# Sheet2.net
KiCad netlist of a schematic drawn in Altium Designer
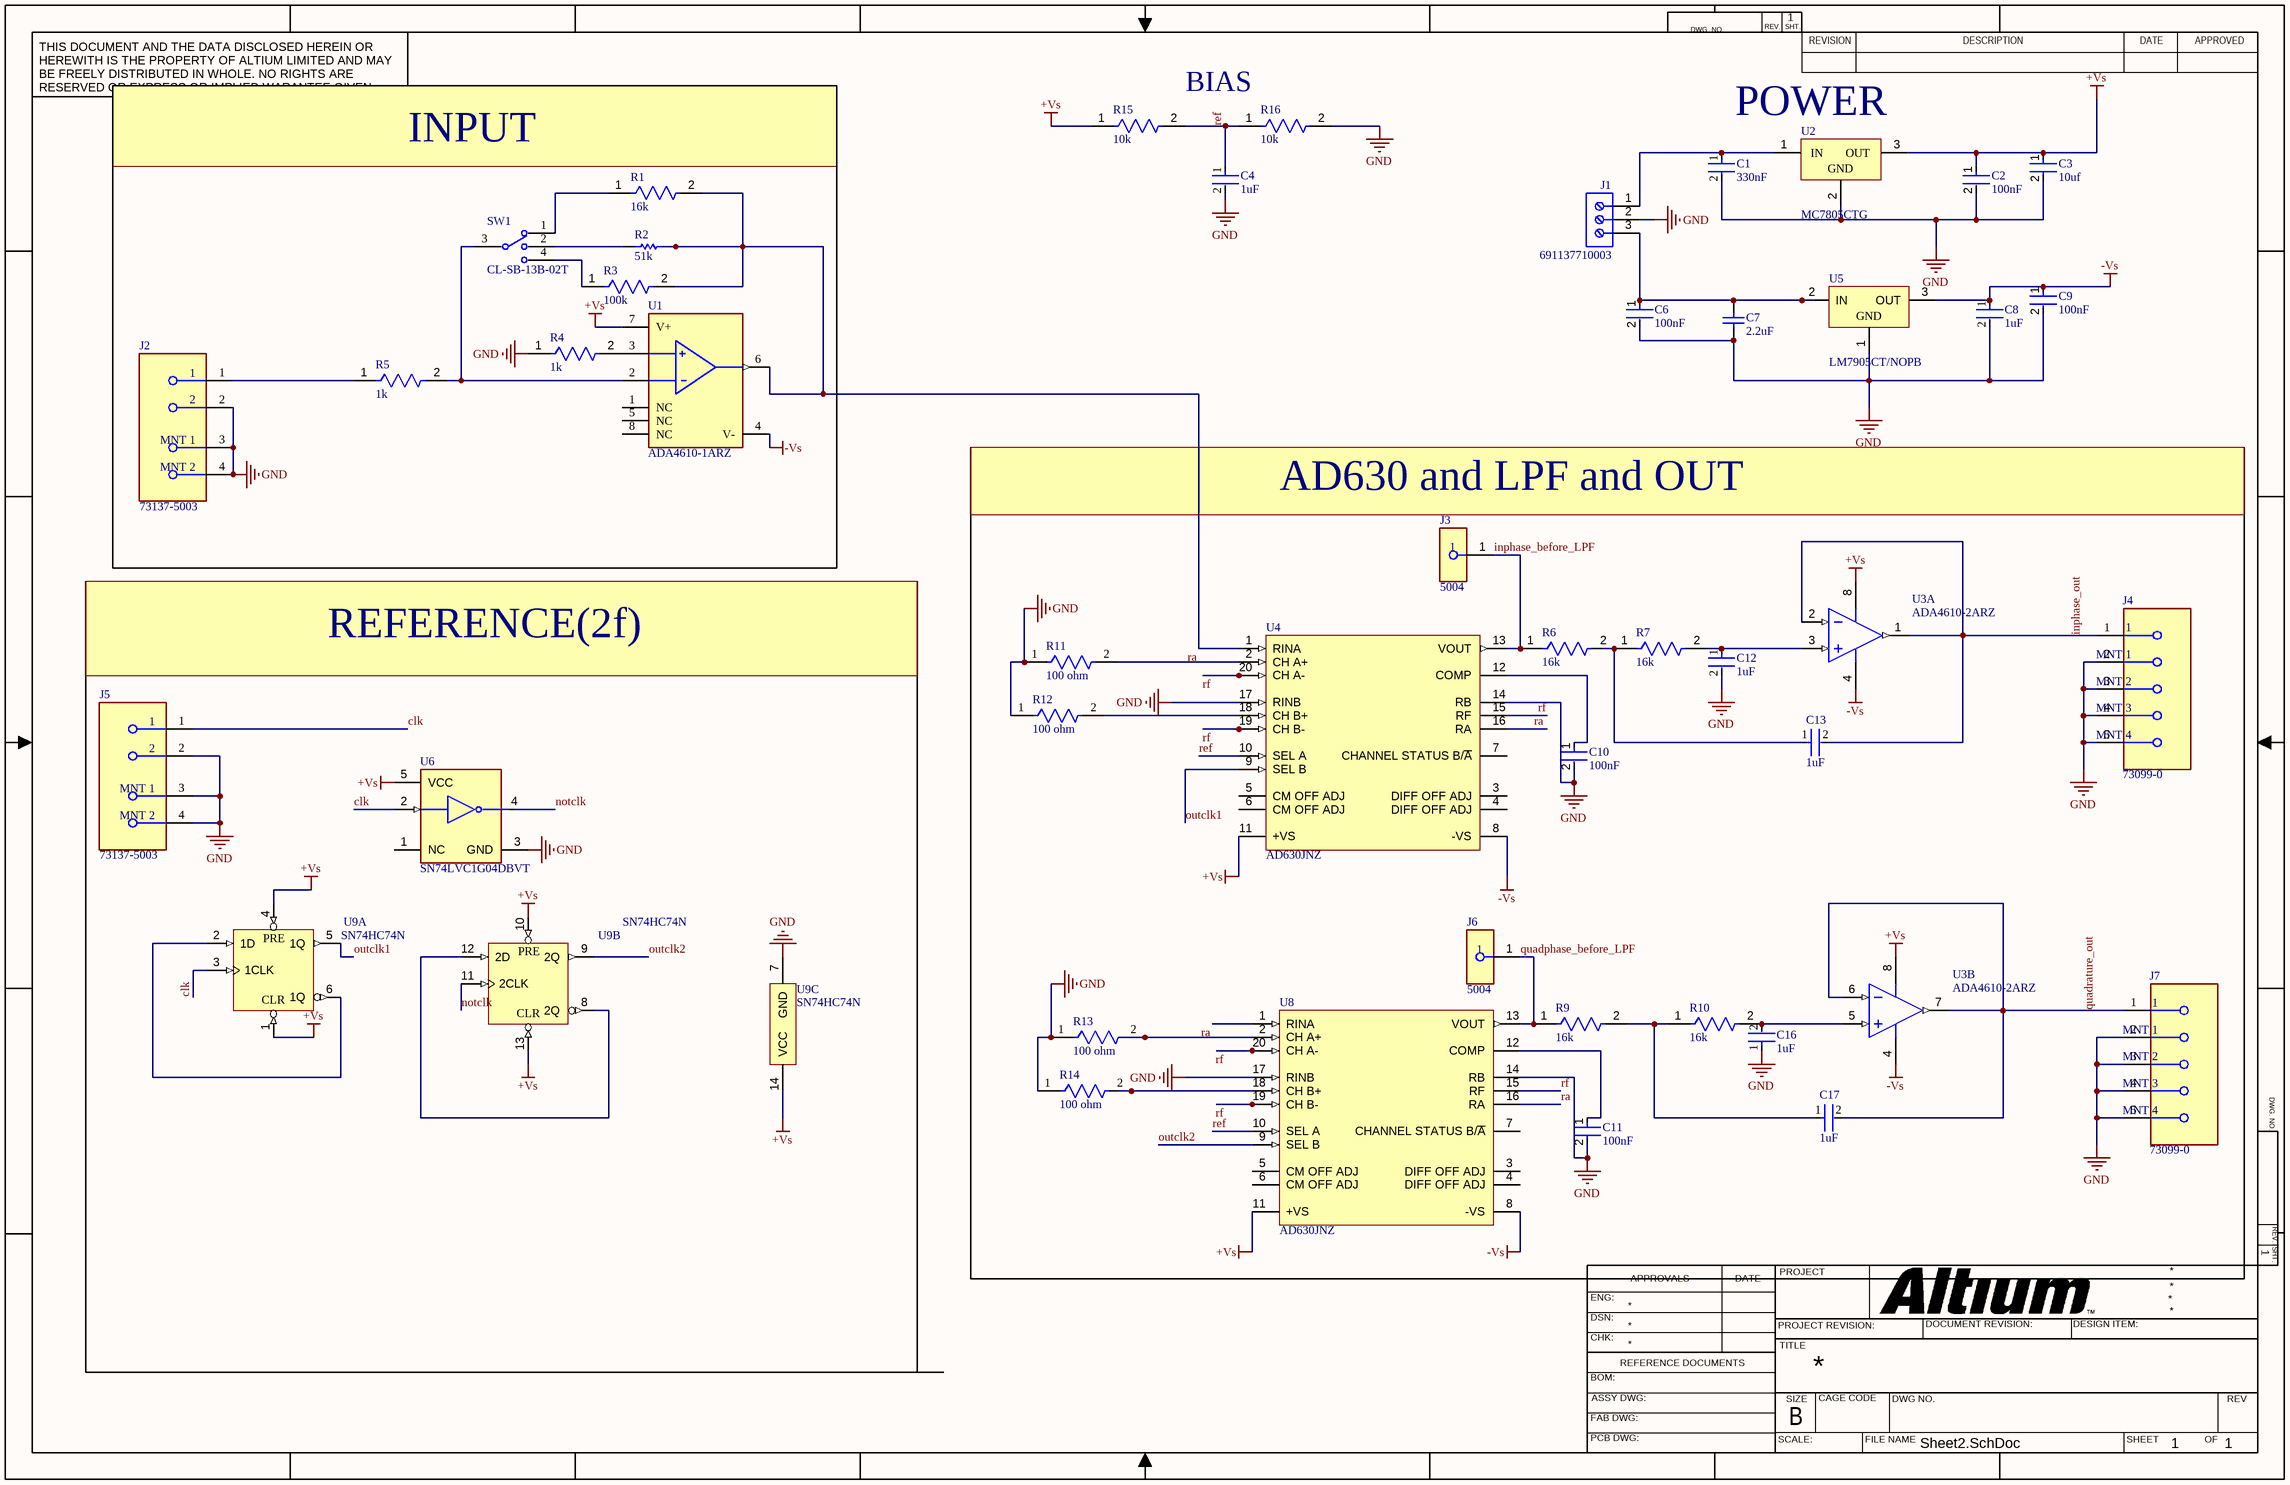
[diagram p0: Sheet2.SchDoc]

(export (version "E")
  (design (tool "Eeschema 10.0.6"))
  (components
    (comp (ref "C1")
      (value "330nF")
      (footprint "FP-GRM155-0_1-MFG")
      (description "GRM155R61H334KE01J Multilayer Ceramic Capacitor, 0.33 uF, 50 V, ± 10%, X5R, 0402 [1005 Metric]")
      (fields (field (name "TOLERANCE") "10%"))
      (libsource (lib "Altium Content Vault") (part "02cd4be3c70576c341d710602a673aa"))
    )
    (comp (ref "C2")
      (value "100nF")
      (footprint "FP-CL21-IPC_C")
      (description "CL21 Series 0805 100nF 50V ±10% Tolerance X7R Multilayer Ceramic Chip Capacitor")
      (fields (field (name "TOLERANCE") "10%") (field (name "VOLTAGE") "50V"))
      (libsource (lib "Altium Content Vault") (part "b4654b650e69147ec39a6b967a45e02"))
    )
    (comp (ref "C3")
      (value "10uf")
      (footprint "FP-CL21-IPC_A")
      (description "CL21 Series 0805 10uF 25V ±10% Tolerance X5R Multilayer Ceramic Chip Capacitor")
      (fields (field (name "TOLERANCE") "10%"))
      (libsource (lib "Altium Content Vault") (part "b4654b650e69147ec39a6b967a45e02"))
    )
    (comp (ref "C4")
      (value "1uF")
      (footprint "FP-GCM188-0_1-MFG")
      (fields (field (name "TOLERANCE") "10%") (field (name "VOLTAGE") "25V"))
      (libsource (lib "Altium Content Vault") (part "02cd4be3c70576c341d710602a673aa"))
    )
    (comp (ref "C6")
      (value "100nF")
      (footprint "FP-CL21-IPC_C")
      (description "CL21 Series 0805 100nF 50V ±10% Tolerance X7R Multilayer Ceramic Chip Capacitor")
      (fields (field (name "TOLERANCE") "10%") (field (name "VOLTAGE") "50V"))
      (libsource (lib "Altium Content Vault") (part "b4654b650e69147ec39a6b967a45e02"))
    )
    (comp (ref "C7")
      (value "2.2uF")
      (footprint "CAPC2013X145X50LL20T25")
      (fields (field (name "MANUFACTURER") "Kemet") (field (name "PART NUMBER") "C0805C225K4RAC7800"))
      (libsource (lib "Altium Content Vault") (part "CAP"))
    )
    (comp (ref "C8")
      (value "1uF")
      (footprint "FP-GCM188-0_1-MFG")
      (fields (field (name "TOLERANCE") "10%") (field (name "VOLTAGE") "25V"))
      (libsource (lib "Altium Content Vault") (part "02cd4be3c70576c341d710602a673aa"))
    )
    (comp (ref "C9")
      (value "100nF")
      (footprint "FP-CL21-IPC_C")
      (description "CL21 Series 0805 100nF 50V ±10% Tolerance X7R Multilayer Ceramic Chip Capacitor")
      (fields (field (name "TOLERANCE") "10%") (field (name "VOLTAGE") "50V"))
      (libsource (lib "Altium Content Vault") (part "b4654b650e69147ec39a6b967a45e02"))
    )
    (comp (ref "C10")
      (value "100nF")
      (footprint "FP-CL21-IPC_C")
      (description "CL21 Series 0805 100nF 50V ±10% Tolerance X7R Multilayer Ceramic Chip Capacitor")
      (fields (field (name "TOLERANCE") "10%") (field (name "VOLTAGE") "50V"))
      (libsource (lib "Altium Content Vault") (part "b4654b650e69147ec39a6b967a45e02"))
    )
    (comp (ref "C11")
      (value "100nF")
      (footprint "FP-CL21-IPC_C")
      (description "CL21 Series 0805 100nF 50V ±10% Tolerance X7R Multilayer Ceramic Chip Capacitor")
      (fields (field (name "TOLERANCE") "10%") (field (name "VOLTAGE") "50V"))
      (libsource (lib "Altium Content Vault") (part "b4654b650e69147ec39a6b967a45e02"))
    )
    (comp (ref "C12")
      (value "1uF")
      (footprint "FP-GCM188-0_1-MFG")
      (fields (field (name "TOLERANCE") "10%") (field (name "VOLTAGE") "25V"))
      (libsource (lib "Altium Content Vault") (part "02cd4be3c70576c341d710602a673aa"))
    )
    (comp (ref "C13")
      (value "1uF")
      (footprint "FP-GCM188-0_1-MFG")
      (fields (field (name "TOLERANCE") "10%") (field (name "VOLTAGE") "25V"))
      (libsource (lib "Altium Content Vault") (part "02cd4be3c70576c341d710602a673aa"))
    )
    (comp (ref "C16")
      (value "1uF")
      (footprint "FP-GCM188-0_1-MFG")
      (fields (field (name "TOLERANCE") "10%") (field (name "VOLTAGE") "25V"))
      (libsource (lib "Altium Content Vault") (part "02cd4be3c70576c341d710602a673aa"))
    )
    (comp (ref "C17")
      (value "1uF")
      (footprint "FP-GCM188-0_1-MFG")
      (fields (field (name "TOLERANCE") "10%") (field (name "VOLTAGE") "25V"))
      (libsource (lib "Altium Content Vault") (part "02cd4be3c70576c341d710602a673aa"))
    )
    (comp (ref "J1")
      (value "691137710003")
      (footprint "691137710003")
      (description "Terminal Block, 5MM Pitch, Horizontal, Pressure Clamp Glow Wire, Pcb, 3PINS, Gr")
      (libsource (lib "Altium Content Vault") (part "TBL - 1R - 03P - Screw"))
    )
    (comp (ref "J2")
      (value "73137-5003")
      (footprint "FP-73137-5003-MFG")
      (description "73137-5003 Connector BNC Female 0Hz To 2GHz 50 Ohm Solder Right Angle Through Hole Gold Tray")
      (libsource (lib "Altium Content Vault") (part "3abcdd43b2a612663cc81d8cccb07ec"))
    )
    (comp (ref "J3")
      (value "5004")
      (footprint "FP-5004-MFG")
      (description "PC TEST POINT MINIATURE YELLOW")
      (fields
        (field (name "MANUFACTURER") "Keystone")
        (field (name "OCTOPART") "https://octopart.com/5004-keystone-28591")
      )
      (libsource (lib "Altium Content Vault") (part "98815daf2f2c152b0c43f5ab9800df6"))
    )
    (comp (ref "J4")
      (value "73099-0")
      (footprint "FP-73099-0-MFG")
      (description "R/A 4MM MOUNTG SAFE JACK/PCB BLK")
      (libsource (lib "Altium Content Vault") (part "a163d97a771fcdd2fd1f1a9264c171f"))
    )
    (comp (ref "J5")
      (value "73137-5003")
      (footprint "FP-73137-5003-MFG")
      (description "73137-5003 Connector BNC Female 0Hz To 2GHz 50 Ohm Solder Right Angle Through Hole Gold Tray")
      (libsource (lib "Altium Content Vault") (part "3abcdd43b2a612663cc81d8cccb07ec"))
    )
    (comp (ref "J6")
      (value "5004")
      (footprint "FP-5004-MFG")
      (description "PC TEST POINT MINIATURE YELLOW")
      (fields
        (field (name "MANUFACTURER") "Keystone")
        (field (name "OCTOPART") "https://octopart.com/5004-keystone-28591")
      )
      (libsource (lib "Altium Content Vault") (part "98815daf2f2c152b0c43f5ab9800df6"))
    )
    (comp (ref "J7")
      (value "73099-0")
      (footprint "FP-73099-0-MFG")
      (description "R/A 4MM MOUNTG SAFE JACK/PCB BLK")
      (libsource (lib "Altium Content Vault") (part "a163d97a771fcdd2fd1f1a9264c171f"))
    )
    (comp (ref "R1")
      (value "16k")
      (footprint "FP-RT0603-MFG")
      (description "RES SMD 16K OHM 1% 1/10W 0603")
      (fields
        (field (name "OCTOPART") "https://octopart.com/rt0603fre0716kl-yageo-1480398")
        (field (name "MANUFACTURER PART NUMBER") "RT0603FRE0716KL")
      )
      (libsource (lib "Altium Content Vault") (part "1029c3af85768c4190bb7ad29bc67b5"))
    )
    (comp (ref "R2")
      (value "51k")
      (footprint "RESC1608X55X25LL10T15")
      (fields (field (name "MANUFACTURER") "Yageo") (field (name "PART NUMBER") "RC0603FR-1351KL"))
      (libsource (lib "Altium Content Vault") (part "RES"))
    )
    (comp (ref "R3")
      (value "100k")
      (footprint "FP-RC0603-0_55-MFG")
      (description "RES SMD 100K OHM 1% 1/10W 0603")
      (fields (field (name "TOLERANCE") "1%"))
      (libsource (lib "Altium Content Vault") (part "1029c3af85768c4190bb7ad29bc67b5"))
    )
    (comp (ref "R4")
      (value "1k")
      (footprint "FP-AC0603-IPC_C")
      (description "RES 1kΩ 1.00% 0.1W 0603")
      (fields (field (name "TOLERANCE") "1%"))
      (libsource (lib "Altium Content Vault") (part "1029c3af85768c4190bb7ad29bc67b5"))
    )
    (comp (ref "R5")
      (value "1k")
      (footprint "FP-AC0603-IPC_C")
      (description "RES 1kΩ 1.00% 0.1W 0603")
      (fields (field (name "TOLERANCE") "1%"))
      (libsource (lib "Altium Content Vault") (part "1029c3af85768c4190bb7ad29bc67b5"))
    )
    (comp (ref "R6")
      (value "16k")
      (footprint "FP-RT0603-MFG")
      (description "RES SMD 16K OHM 1% 1/10W 0603")
      (fields
        (field (name "OCTOPART") "https://octopart.com/rt0603fre0716kl-yageo-1480398")
        (field (name "MANUFACTURER PART NUMBER") "RT0603FRE0716KL")
      )
      (libsource (lib "Altium Content Vault") (part "1029c3af85768c4190bb7ad29bc67b5"))
    )
    (comp (ref "R7")
      (value "16k")
      (footprint "FP-RT0603-MFG")
      (description "RES SMD 16K OHM 1% 1/10W 0603")
      (fields
        (field (name "OCTOPART") "https://octopart.com/rt0603fre0716kl-yageo-1480398")
        (field (name "MANUFACTURER PART NUMBER") "RT0603FRE0716KL")
      )
      (libsource (lib "Altium Content Vault") (part "1029c3af85768c4190bb7ad29bc67b5"))
    )
    (comp (ref "R9")
      (value "16k")
      (footprint "FP-RT0603-MFG")
      (description "RES SMD 16K OHM 1% 1/10W 0603")
      (fields
        (field (name "OCTOPART") "https://octopart.com/rt0603fre0716kl-yageo-1480398")
        (field (name "MANUFACTURER PART NUMBER") "RT0603FRE0716KL")
      )
      (libsource (lib "Altium Content Vault") (part "1029c3af85768c4190bb7ad29bc67b5"))
    )
    (comp (ref "R10")
      (value "16k")
      (footprint "FP-RT0603-MFG")
      (description "RES SMD 16K OHM 1% 1/10W 0603")
      (fields
        (field (name "OCTOPART") "https://octopart.com/rt0603fre0716kl-yageo-1480398")
        (field (name "MANUFACTURER PART NUMBER") "RT0603FRE0716KL")
      )
      (libsource (lib "Altium Content Vault") (part "1029c3af85768c4190bb7ad29bc67b5"))
    )
    (comp (ref "R11")
      (value "100 ohm")
      (footprint "FP-RC0603-0_55-MFG")
      (fields (field (name "TOLERANCE") "1%"))
      (libsource (lib "Altium Content Vault") (part "1029c3af85768c4190bb7ad29bc67b5"))
    )
    (comp (ref "R12")
      (value "100 ohm")
      (footprint "FP-RC0603-0_55-MFG")
      (fields (field (name "TOLERANCE") "1%"))
      (libsource (lib "Altium Content Vault") (part "1029c3af85768c4190bb7ad29bc67b5"))
    )
    (comp (ref "R13")
      (value "100 ohm")
      (footprint "FP-RC0603-0_55-MFG")
      (fields (field (name "TOLERANCE") "1%"))
      (libsource (lib "Altium Content Vault") (part "1029c3af85768c4190bb7ad29bc67b5"))
    )
    (comp (ref "R14")
      (value "100 ohm")
      (footprint "FP-RC0603-0_55-MFG")
      (fields (field (name "TOLERANCE") "1%"))
      (libsource (lib "Altium Content Vault") (part "1029c3af85768c4190bb7ad29bc67b5"))
    )
    (comp (ref "R15")
      (value "10k")
      (footprint "FP-RC0603-0_55-IPC_C")
      (description "RES 10K OHM 1% 1/10W 0603")
      (fields (field (name "TOLERANCE") "1%"))
      (libsource (lib "Altium Content Vault") (part "1029c3af85768c4190bb7ad29bc67b5"))
    )
    (comp (ref "R16")
      (value "10k")
      (footprint "FP-RC0603-0_55-IPC_C")
      (description "RES 10K OHM 1% 1/10W 0603")
      (fields (field (name "TOLERANCE") "1%"))
      (libsource (lib "Altium Content Vault") (part "1029c3af85768c4190bb7ad29bc67b5"))
    )
    (comp (ref "SW1")
      (value "CL-SB-13B-02T")
      (footprint "FP-CL-SB-13B-02T-MFG")
      (description "CL-SB-13B-02T Switch Slide ON-ON-ON SP3T Top 200mA 12VDC 10000Cycles Gullwing T/R")
      (libsource (lib "Altium Content Vault") (part "5552a05cdd07c74f2f3fb1217988f51"))
    )
    (comp (ref "U1")
      (value "ADA4610-1ARZ")
      (footprint "FP-R-8-IPC_A")
      (description "IC OPAMP JFET 1 CIRCUIT 8SOIC")
      (libsource (lib "Altium Content Vault") (part "ddfbf3f15953d8f4fc9e3157209a166"))
    )
    (comp (ref "U2")
      (value "MC7805CTG")
      (footprint "ONSC-TO-220-3-221AB-01")
      (description "Positive Voltage Regulator, 1 A, 5 V, 0 to 125 degC, 3-Pin TO-220, RoHS, Tube")
      (fields (field (name "MANUFACTURER") "ON Semiconductor"))
      (libsource (lib "Altium Content Vault") (part "ONSC-MC7805CTG-TO-220-3"))
    )
    (comp (ref "U3")
      (value "ADA4610-2ARZ")
      (footprint "ADI-R-8_N")
      (fields (field (name "MANUFACTURER") "Analog Devices") (field (name "GENERIC PART NUMBER") "ADA4610-2"))
      (libsource (lib "Altium Content Vault") (part "ADI-OP29X-R-8"))
    )
    (comp (ref "U4")
      (value "AD630JNZ")
      (footprint "ADI-N-20")
      (description "Balanced Modulator/Demodulator, 2MHz Max RF Frequency, N-20, 18 Tube")
      (libsource (lib "Altium Content Vault") (part "ADI-AD630-N-20"))
    )
    (comp (ref "U5")
      (value "LM7905CT/NOPB")
      (footprint "NDE0003A")
      (description "3-Terminal Negative Regulator, 3-pin TO-220, Pb-Free")
      (fields (field (name "MANUFACTURER") "Texas Instruments"))
      (libsource (lib "Altium Content Vault") (part "PM-REG-LM7905-SIL3"))
    )
    (comp (ref "U6")
      (value "SN74LVC1G04DBVT")
      (footprint "FP-DBV0005A-IPC_C")
      (description "IC INVERTER 1CH 1-INP SOT23-5")
      (fields
        (field (name "OCTOPART") "https://octopart.com/sn74lvc1g04dbvt-texas+instruments-881539")
        (field (name "MANUFACTURER") "Texas Instruments")
      )
      (libsource (lib "Altium Content Vault") (part "d8ebd454d5f67517583d36c9dc32b5e"))
    )
    (comp (ref "U8")
      (value "AD630JNZ")
      (footprint "ADI-N-20")
      (description "Balanced Modulator/Demodulator, 2MHz Max RF Frequency, N-20, 18 Tube")
      (libsource (lib "Altium Content Vault") (part "ADI-AD630-N-20"))
    )
    (comp (ref "U9")
      (value "SN74HC74N")
      (footprint "N0014A")
      (description "Dual D-Type Positive-Edge-Triggered Flip-Flops With Clear and Preset, N0014A, TUBE")
      (fields
        (field (name "MANUFACTURER") "Texas Instruments")
        (field (name "GENERIC PART NUMBER") "SN74HC74")
      )
      (libsource (lib "") (part "TI-CD_SNX4XXXX74X-14_1"))
    )
  )
  (nets
    (net (code "1") (name "+Vs") (class "Default")
      (node (ref "C2") (pin "1") (pinfunction "1_1") (pintype "passive"))
      (node (ref "C3") (pin "1") (pinfunction "1_1") (pintype "passive"))
      (node (ref "R15") (pin "1") (pinfunction "1_1") (pintype "passive"))
      (node (ref "U1") (pin "7") (pinfunction "V+_7") (pintype "power_in"))
      (node (ref "U2") (pin "3") (pinfunction "OUT_3") (pintype "power_in"))
      (node (ref "U3") (pin "8") (pinfunction "+V_8") (pintype "power_in"))
      (node (ref "U4") (pin "11") (pinfunction "+VS_11") (pintype "power_in"))
      (node (ref "U6") (pin "5") (pinfunction "VCC_5") (pintype "power_in"))
      (node (ref "U8") (pin "11") (pinfunction "+VS_11") (pintype "power_in"))
      (node (ref "U9") (pin "1") (pinfunction "1~{CLR}_1") (pintype "input"))
      (node (ref "U9") (pin "10") (pinfunction "2~{PRE}_10") (pintype "input"))
      (node (ref "U9") (pin "13") (pinfunction "2~{CLR}_13") (pintype "input"))
      (node (ref "U9") (pin "14") (pinfunction "VCC_14") (pintype "power_in"))
      (node (ref "U9") (pin "4") (pinfunction "1~{PRE}_4") (pintype "input"))
    )
    (net (code "2") (name "-Vs") (class "Default")
      (node (ref "C8") (pin "1") (pinfunction "1_1") (pintype "passive"))
      (node (ref "C9") (pin "1") (pinfunction "1_1") (pintype "passive"))
      (node (ref "U1") (pin "4") (pinfunction "V-_4") (pintype "power_in"))
      (node (ref "U3") (pin "4") (pinfunction "-V_4") (pintype "power_in"))
      (node (ref "U4") (pin "8") (pinfunction "-VS_8") (pintype "power_in"))
      (node (ref "U5") (pin "3") (pinfunction "OUT_3") (pintype "power_in"))
      (node (ref "U8") (pin "8") (pinfunction "-VS_8") (pintype "power_in"))
    )
    (net (code "3") (name "/clk") (class "Default")
      (node (ref "J5") (pin "1") (pinfunction "1_1") (pintype "passive"))
      (node (ref "U6") (pin "2") (pinfunction "A_2") (pintype "input"))
      (node (ref "U9") (pin "3") (pinfunction "1CLK_3") (pintype "input"))
    )
    (net (code "4") (name "/inphase_before_LPF") (class "Default")
      (node (ref "J3") (pin "1") (pinfunction "1_1") (pintype "passive"))
      (node (ref "R6") (pin "1") (pinfunction "1_1") (pintype "passive"))
      (node (ref "U4") (pin "13") (pinfunction "VOUT_13") (pintype "output"))
    )
    (net (code "5") (name "/inphase_out") (class "Default")
      (node (ref "C13") (pin "2") (pinfunction "2_2") (pintype "passive"))
      (node (ref "J4") (pin "1") (pinfunction "1_1") (pintype "passive"))
      (node (ref "U3") (pin "1") (pinfunction "OUT_A_1") (pintype "output"))
      (node (ref "U3") (pin "2") (pinfunction "-IN_A_2") (pintype "input"))
    )
    (net (code "6") (name "/notclk") (class "Default")
      (node (ref "U6") (pin "4") (pinfunction "Y_4") (pintype "output"))
      (node (ref "U9") (pin "11") (pinfunction "2CLK_11") (pintype "input"))
    )
    (net (code "7") (name "/outclk1") (class "Default")
      (node (ref "U4") (pin "9") (pinfunction "SEL_B_9") (pintype "input"))
      (node (ref "U9") (pin "5") (pinfunction "1Q_5") (pintype "output"))
    )
    (net (code "8") (name "/outclk2") (class "Default")
      (node (ref "U8") (pin "9") (pinfunction "SEL_B_9") (pintype "input"))
      (node (ref "U9") (pin "9") (pinfunction "2Q_9") (pintype "output"))
    )
    (net (code "9") (name "/quadphase_before_LPF") (class "Default")
      (node (ref "J6") (pin "1") (pinfunction "1_1") (pintype "passive"))
      (node (ref "R9") (pin "1") (pinfunction "1_1") (pintype "passive"))
      (node (ref "U8") (pin "13") (pinfunction "VOUT_13") (pintype "output"))
    )
    (net (code "10") (name "/quadrature_out") (class "Default")
      (node (ref "C17") (pin "2") (pinfunction "2_2") (pintype "passive"))
      (node (ref "J7") (pin "1") (pinfunction "1_1") (pintype "passive"))
      (node (ref "U3") (pin "6") (pinfunction "-IN_B_6") (pintype "input"))
      (node (ref "U3") (pin "7") (pinfunction "OUT_B_7") (pintype "output"))
    )
    (net (code "11") (name "/ra") (class "Default")
      (node (ref "R1") (pin "2") (pinfunction "2_2") (pintype "passive"))
      (node (ref "R2") (pin "2") (pinfunction "2_2") (pintype "passive"))
      (node (ref "R3") (pin "2") (pinfunction "2_2") (pintype "passive"))
      (node (ref "U1") (pin "6") (pinfunction "OUT_6") (pintype "output"))
      (node (ref "U4") (pin "1") (pinfunction "RINA_1") (pintype "input"))
      (node (ref "U4") (pin "16") (pinfunction "RA_16") (pintype "passive"))
      (node (ref "U8") (pin "1") (pinfunction "RINA_1") (pintype "input"))
      (node (ref "U8") (pin "16") (pinfunction "RA_16") (pintype "passive"))
    )
    (net (code "12") (name "/ref") (class "Default")
      (node (ref "C4") (pin "1") (pinfunction "1_1") (pintype "passive"))
      (node (ref "R15") (pin "2") (pinfunction "2_2") (pintype "passive"))
      (node (ref "R16") (pin "1") (pinfunction "1_1") (pintype "passive"))
      (node (ref "U4") (pin "10") (pinfunction "SEL_A_10") (pintype "input"))
      (node (ref "U8") (pin "10") (pinfunction "SEL_A_10") (pintype "input"))
    )
    (net (code "13") (name "/rf") (class "Default")
      (node (ref "U4") (pin "15") (pinfunction "RF_15") (pintype "passive"))
      (node (ref "U4") (pin "19") (pinfunction "CH_B-_19") (pintype "input"))
      (node (ref "U4") (pin "20") (pinfunction "CH_A-_20") (pintype "input"))
      (node (ref "U8") (pin "15") (pinfunction "RF_15") (pintype "passive"))
      (node (ref "U8") (pin "19") (pinfunction "CH_B-_19") (pintype "input"))
      (node (ref "U8") (pin "20") (pinfunction "CH_A-_20") (pintype "input"))
    )
    (net (code "14") (name "GND") (class "Default")
      (node (ref "C1") (pin "2") (pinfunction "2_2") (pintype "passive"))
      (node (ref "C10") (pin "2") (pinfunction "2_2") (pintype "passive"))
      (node (ref "C11") (pin "2") (pinfunction "2_2") (pintype "passive"))
      (node (ref "C12") (pin "2") (pinfunction "2_2") (pintype "passive"))
      (node (ref "C16") (pin "1") (pinfunction "1_1") (pintype "passive"))
      (node (ref "C2") (pin "2") (pinfunction "2_2") (pintype "passive"))
      (node (ref "C3") (pin "2") (pinfunction "2_2") (pintype "passive"))
      (node (ref "C4") (pin "2") (pinfunction "2_2") (pintype "passive"))
      (node (ref "C6") (pin "2") (pinfunction "2_2") (pintype "passive"))
      (node (ref "C7") (pin "1") (pinfunction "1_1") (pintype "passive"))
      (node (ref "C8") (pin "2") (pinfunction "2_2") (pintype "passive"))
      (node (ref "C9") (pin "2") (pinfunction "2_2") (pintype "passive"))
      (node (ref "J1") (pin "2") (pinfunction "2_2") (pintype "passive"))
      (node (ref "J2") (pin "2") (pinfunction "2_2") (pintype "passive"))
      (node (ref "J2") (pin "3") (pinfunction "MNT_1_3") (pintype "passive"))
      (node (ref "J2") (pin "4") (pinfunction "MNT_2_4") (pintype "passive"))
      (node (ref "J4") (pin "2") (pinfunction "MNT_1_2") (pintype "passive"))
      (node (ref "J4") (pin "3") (pinfunction "MNT_2_3") (pintype "passive"))
      (node (ref "J4") (pin "4") (pinfunction "MNT_3_4") (pintype "passive"))
      (node (ref "J4") (pin "5") (pinfunction "MNT_4_5") (pintype "passive"))
      (node (ref "J5") (pin "2") (pinfunction "2_2") (pintype "passive"))
      (node (ref "J5") (pin "3") (pinfunction "MNT_1_3") (pintype "passive"))
      (node (ref "J5") (pin "4") (pinfunction "MNT_2_4") (pintype "passive"))
      (node (ref "J7") (pin "2") (pinfunction "MNT_1_2") (pintype "passive"))
      (node (ref "J7") (pin "3") (pinfunction "MNT_2_3") (pintype "passive"))
      (node (ref "J7") (pin "4") (pinfunction "MNT_3_4") (pintype "passive"))
      (node (ref "J7") (pin "5") (pinfunction "MNT_4_5") (pintype "passive"))
      (node (ref "R11") (pin "1") (pinfunction "1_1") (pintype "passive"))
      (node (ref "R12") (pin "1") (pinfunction "1_1") (pintype "passive"))
      (node (ref "R13") (pin "1") (pinfunction "1_1") (pintype "passive"))
      (node (ref "R14") (pin "1") (pinfunction "1_1") (pintype "passive"))
      (node (ref "R16") (pin "2") (pinfunction "2_2") (pintype "passive"))
      (node (ref "R4") (pin "1") (pinfunction "1_1") (pintype "passive"))
      (node (ref "U2") (pin "2") (pinfunction "GND_2") (pintype "power_in"))
      (node (ref "U4") (pin "14") (pinfunction "RB_14") (pintype "passive"))
      (node (ref "U4") (pin "17") (pinfunction "RINB_17") (pintype "input"))
      (node (ref "U5") (pin "1") (pinfunction "GND_1") (pintype "power_in"))
      (node (ref "U6") (pin "3") (pinfunction "GND_3") (pintype "power_in"))
      (node (ref "U8") (pin "14") (pinfunction "RB_14") (pintype "passive"))
      (node (ref "U8") (pin "17") (pinfunction "RINB_17") (pintype "input"))
      (node (ref "U9") (pin "7") (pinfunction "GND_7") (pintype "power_in"))
    )
    (net (code "15") (name "Net-(C13-Pad1)") (class "Default")
      (node (ref "C13") (pin "1") (pinfunction "1_1") (pintype "passive"))
      (node (ref "R6") (pin "2") (pinfunction "2_2") (pintype "passive"))
      (node (ref "R7") (pin "1") (pinfunction "1_1") (pintype "passive"))
    )
    (net (code "16") (name "Net-(C17-Pad1)") (class "Default")
      (node (ref "C17") (pin "1") (pinfunction "1_1") (pintype "passive"))
      (node (ref "R10") (pin "1") (pinfunction "1_1") (pintype "passive"))
      (node (ref "R9") (pin "2") (pinfunction "2_2") (pintype "passive"))
    )
    (net (code "17") (name "Net-(J2-Pad1)") (class "Default")
      (node (ref "J2") (pin "1") (pinfunction "1_1") (pintype "passive"))
      (node (ref "R5") (pin "1") (pinfunction "1_1") (pintype "passive"))
    )
    (net (code "18") (name "Net-(R1-Pad1)") (class "Default")
      (node (ref "R1") (pin "1") (pinfunction "1_1") (pintype "passive"))
      (node (ref "SW1") (pin "1") (pinfunction "1_1") (pintype "passive"))
    )
    (net (code "19") (name "Net-(R2-Pad1)") (class "Default")
      (node (ref "R2") (pin "1") (pinfunction "1_1") (pintype "passive"))
      (node (ref "SW1") (pin "2") (pinfunction "2_2") (pintype "passive"))
    )
    (net (code "20") (name "Net-(R3-Pad1)") (class "Default")
      (node (ref "R3") (pin "1") (pinfunction "1_1") (pintype "passive"))
      (node (ref "SW1") (pin "4") (pinfunction "4_4") (pintype "passive"))
    )
    (net (code "21") (name "Net-(SW1-C)") (class "Default")
      (node (ref "R5") (pin "2") (pinfunction "2_2") (pintype "passive"))
      (node (ref "SW1") (pin "3") (pinfunction "C_3") (pintype "passive"))
      (node (ref "U1") (pin "2") (pinfunction "-IN_2") (pintype "tri_state"))
    )
    (net (code "22") (name "Net-(U1-+IN)") (class "Default")
      (node (ref "R4") (pin "2") (pinfunction "2_2") (pintype "passive"))
      (node (ref "U1") (pin "3") (pinfunction "+IN_3") (pintype "tri_state"))
    )
    (net (code "23") (name "Net-(U2-IN)") (class "Default")
      (node (ref "C1") (pin "1") (pinfunction "1_1") (pintype "passive"))
      (node (ref "J1") (pin "1") (pinfunction "1_1") (pintype "passive"))
      (node (ref "U2") (pin "1") (pinfunction "IN_1") (pintype "power_in"))
    )
    (net (code "24") (name "Net-(U3A-+IN_A)") (class "Default")
      (node (ref "C12") (pin "1") (pinfunction "1_1") (pintype "passive"))
      (node (ref "R7") (pin "2") (pinfunction "2_2") (pintype "passive"))
      (node (ref "U3") (pin "3") (pinfunction "+IN_A_3") (pintype "input"))
    )
    (net (code "25") (name "Net-(U3B-+IN_B)") (class "Default")
      (node (ref "C16") (pin "2") (pinfunction "2_2") (pintype "passive"))
      (node (ref "R10") (pin "2") (pinfunction "2_2") (pintype "passive"))
      (node (ref "U3") (pin "5") (pinfunction "+IN_B_5") (pintype "input"))
    )
    (net (code "26") (name "Net-(U4-CH_A+)") (class "Default")
      (node (ref "R11") (pin "2") (pinfunction "2_2") (pintype "passive"))
      (node (ref "U4") (pin "2") (pinfunction "CH_A+_2") (pintype "input"))
    )
    (net (code "27") (name "Net-(U4-CH_B+)") (class "Default")
      (node (ref "R12") (pin "2") (pinfunction "2_2") (pintype "passive"))
      (node (ref "U4") (pin "18") (pinfunction "CH_B+_18") (pintype "input"))
    )
    (net (code "28") (name "Net-(U4-COMP)") (class "Default")
      (node (ref "C10") (pin "1") (pinfunction "1_1") (pintype "passive"))
      (node (ref "U4") (pin "12") (pinfunction "COMP_12") (pintype "passive"))
    )
    (net (code "29") (name "Net-(U5-IN)") (class "Default")
      (node (ref "C6") (pin "1") (pinfunction "1_1") (pintype "passive"))
      (node (ref "C7") (pin "2") (pinfunction "2_2") (pintype "passive"))
      (node (ref "J1") (pin "3") (pinfunction "3_3") (pintype "passive"))
      (node (ref "U5") (pin "2") (pinfunction "IN_2") (pintype "power_in"))
    )
    (net (code "30") (name "Net-(U8-CH_A+)") (class "Default")
      (node (ref "R13") (pin "2") (pinfunction "2_2") (pintype "passive"))
      (node (ref "U8") (pin "2") (pinfunction "CH_A+_2") (pintype "input"))
    )
    (net (code "31") (name "Net-(U8-CH_B+)") (class "Default")
      (node (ref "R14") (pin "2") (pinfunction "2_2") (pintype "passive"))
      (node (ref "U8") (pin "18") (pinfunction "CH_B+_18") (pintype "input"))
    )
    (net (code "32") (name "Net-(U8-COMP)") (class "Default")
      (node (ref "C11") (pin "1") (pinfunction "1_1") (pintype "passive"))
      (node (ref "U8") (pin "12") (pinfunction "COMP_12") (pintype "passive"))
    )
    (net (code "33") (name "Net-(U9A-1D)") (class "Default")
      (node (ref "U9") (pin "2") (pinfunction "1D_2") (pintype "input"))
      (node (ref "U9") (pin "6") (pinfunction "1Q_6") (pintype "output"))
    )
    (net (code "34") (name "Net-(U9B-2D)") (class "Default")
      (node (ref "U9") (pin "12") (pinfunction "2D_12") (pintype "input"))
      (node (ref "U9") (pin "8") (pinfunction "2Q_8") (pintype "output"))
    )
    (net (code "35") (name "unconnected-(U1-NC-Pad1)") (class "Default")
      (node (ref "U1") (pin "1") (pinfunction "NC_1") (pintype "passive"))
    )
    (net (code "36") (name "unconnected-(U1-NC-Pad5)") (class "Default")
      (node (ref "U1") (pin "5") (pinfunction "NC_5") (pintype "passive"))
    )
    (net (code "37") (name "unconnected-(U1-NC-Pad8)") (class "Default")
      (node (ref "U1") (pin "8") (pinfunction "NC_8") (pintype "passive"))
    )
    (net (code "38") (name "unconnected-(U4-CHANNEL_STATUS_B{slash}~{A}-Pad7)") (class "Default")
      (node (ref "U4") (pin "7") (pinfunction "CHANNEL_STATUS_B/~{A}_7") (pintype "open_collector"))
    )
    (net (code "39") (name "unconnected-(U4-CM_OFF_ADJ-Pad5)") (class "Default")
      (node (ref "U4") (pin "5") (pinfunction "CM_OFF_ADJ_5") (pintype "passive"))
    )
    (net (code "40") (name "unconnected-(U4-CM_OFF_ADJ-Pad6)") (class "Default")
      (node (ref "U4") (pin "6") (pinfunction "CM_OFF_ADJ_6") (pintype "passive"))
    )
    (net (code "41") (name "unconnected-(U4-DIFF_OFF_ADJ-Pad3)") (class "Default")
      (node (ref "U4") (pin "3") (pinfunction "DIFF_OFF_ADJ_3") (pintype "passive"))
    )
    (net (code "42") (name "unconnected-(U4-DIFF_OFF_ADJ-Pad4)") (class "Default")
      (node (ref "U4") (pin "4") (pinfunction "DIFF_OFF_ADJ_4") (pintype "passive"))
    )
    (net (code "43") (name "unconnected-(U6-NC-Pad1)") (class "Default")
      (node (ref "U6") (pin "1") (pinfunction "NC_1") (pintype "passive"))
    )
    (net (code "44") (name "unconnected-(U8-CHANNEL_STATUS_B{slash}~{A}-Pad7)") (class "Default")
      (node (ref "U8") (pin "7") (pinfunction "CHANNEL_STATUS_B/~{A}_7") (pintype "open_collector"))
    )
    (net (code "45") (name "unconnected-(U8-CM_OFF_ADJ-Pad5)") (class "Default")
      (node (ref "U8") (pin "5") (pinfunction "CM_OFF_ADJ_5") (pintype "passive"))
    )
    (net (code "46") (name "unconnected-(U8-CM_OFF_ADJ-Pad6)") (class "Default")
      (node (ref "U8") (pin "6") (pinfunction "CM_OFF_ADJ_6") (pintype "passive"))
    )
    (net (code "47") (name "unconnected-(U8-DIFF_OFF_ADJ-Pad3)") (class "Default")
      (node (ref "U8") (pin "3") (pinfunction "DIFF_OFF_ADJ_3") (pintype "passive"))
    )
    (net (code "48") (name "unconnected-(U8-DIFF_OFF_ADJ-Pad4)") (class "Default")
      (node (ref "U8") (pin "4") (pinfunction "DIFF_OFF_ADJ_4") (pintype "passive"))
    )
  )
)
